# design.net
KiCad netlist of a schematic drawn in Altium Designer
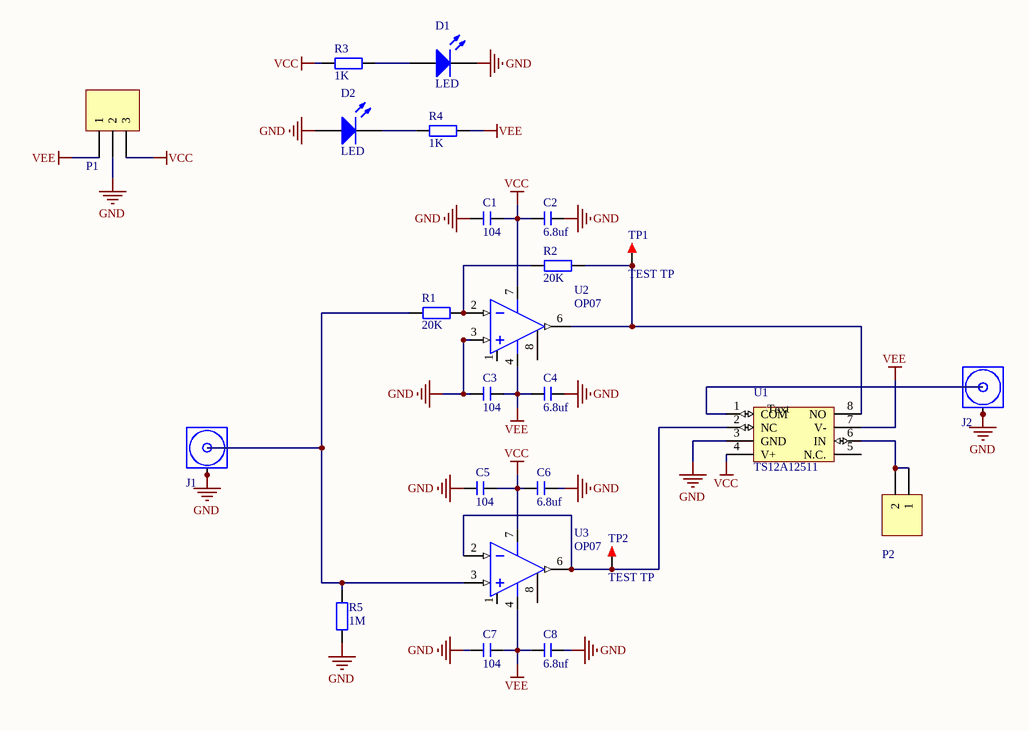
[diagram p0: 相敏检波器.SchDoc]

(export (version "E")
  (design (tool "Eeschema 10.0.6"))
  (components
    (comp (ref "C1")
      (value "104")
      (footprint "C 0805")
      (description "无极性贴片电容")
      (fields (field (name "版权归属") "源创客"))
      (libsource (lib "电阻-电容-电感") (part "C"))
    )
    (comp (ref "C2")
      (value "6.8uf")
      (footprint "C 0805")
      (description "无极性贴片电容")
      (fields (field (name "版权归属") "源创客"))
      (libsource (lib "电阻-电容-电感") (part "C"))
    )
    (comp (ref "C3")
      (value "104")
      (footprint "C 0805")
      (description "无极性贴片电容")
      (fields (field (name "版权归属") "源创客"))
      (libsource (lib "电阻-电容-电感") (part "C"))
    )
    (comp (ref "C4")
      (value "6.8uf")
      (footprint "C 0805")
      (description "无极性贴片电容")
      (fields (field (name "版权归属") "源创客"))
      (libsource (lib "电阻-电容-电感") (part "C"))
    )
    (comp (ref "C5")
      (value "104")
      (footprint "C 0805")
      (description "无极性贴片电容")
      (fields (field (name "版权归属") "源创客"))
      (libsource (lib "电阻-电容-电感") (part "C"))
    )
    (comp (ref "C6")
      (value "6.8uf")
      (footprint "C 0805")
      (description "无极性贴片电容")
      (fields (field (name "版权归属") "源创客"))
      (libsource (lib "电阻-电容-电感") (part "C"))
    )
    (comp (ref "C7")
      (value "104")
      (footprint "C 0805")
      (description "无极性贴片电容")
      (fields (field (name "版权归属") "源创客"))
      (libsource (lib "电阻-电容-电感") (part "C"))
    )
    (comp (ref "C8")
      (value "6.8uf")
      (footprint "C 0805")
      (description "无极性贴片电容")
      (fields (field (name "版权归属") "源创客"))
      (libsource (lib "电阻-电容-电感") (part "C"))
    )
    (comp (ref "D1")
      (value "LED")
      (footprint "LED_0805")
      (description "发光二极管")
      (fields (field (name "PUBLISHER") "Altium Limited"))
      (libsource (lib "LIB") (part "LED"))
    )
    (comp (ref "D2")
      (value "LED")
      (footprint "LED_0805")
      (description "发光二极管")
      (fields (field (name "PUBLISHER") "Altium Limited"))
      (libsource (lib "LIB") (part "LED"))
    )
    (comp (ref "J1") (value "COAX") (footprint "MCX5.08-5-H") (libsource (lib "LIB") (part "COAX")))
    (comp (ref "J2") (value "COAX") (footprint "MCX5.08-5-H") (libsource (lib "LIB") (part "COAX")))
    (comp (ref "P1")
      (value "Header 3")
      (footprint "HDR3X1_B2")
      (description "接插件")
      (fields (field (name "PUBLISHER") "Altium Limited"))
      (libsource (lib "LIB") (part "Header 3"))
    )
    (comp (ref "P2")
      (value "Header 2")
      (footprint "HDR2X1_B2")
      (description "接插件")
      (fields (field (name "PUBLISHER") "Altium Limited"))
      (libsource (lib "LIB") (part "Header 2"))
    )
    (comp (ref "R1")
      (value "20K")
      (footprint "R 0805")
      (description "贴片电阻")
      (fields (field (name "版权归属") "源创客"))
      (libsource (lib "电阻-电容-电感") (part "R"))
    )
    (comp (ref "R2")
      (value "20K")
      (footprint "R 0805")
      (description "贴片电阻")
      (fields (field (name "版权归属") "源创客"))
      (libsource (lib "电阻-电容-电感") (part "R"))
    )
    (comp (ref "R3")
      (value "1K")
      (footprint "R 0805")
      (description "贴片电阻")
      (fields (field (name "版权归属") "源创客"))
      (libsource (lib "电阻-电容-电感") (part "R"))
    )
    (comp (ref "R4")
      (value "1K")
      (footprint "R 0805")
      (description "贴片电阻")
      (fields (field (name "版权归属") "源创客"))
      (libsource (lib "电阻-电容-电感") (part "R"))
    )
    (comp (ref "R5")
      (value "1M")
      (footprint "R 0805")
      (description "贴片电阻")
      (fields (field (name "版权归属") "源创客"))
      (libsource (lib "电阻-电容-电感") (part "R"))
    )
    (comp (ref "TP1")
      (value "TEST TP")
      (footprint "TEST TP1.4_B")
      (description "测试环")
      (fields (field (name "版权归属") "源创客"))
      (libsource (lib "未分类器件") (part "TEST TP"))
    )
    (comp (ref "TP2")
      (value "TEST TP")
      (footprint "TEST TP1.4_B")
      (description "测试环")
      (fields (field (name "版权归属") "源创客"))
      (libsource (lib "未分类器件") (part "TEST TP"))
    )
    (comp (ref "U1")
      (value "TS12A12511")
      (footprint "SOT23-8N")
      (description "具有负信号功能的 5Ω 单通道 SPDT 开关")
      (libsource (lib "LIB") (part "TS12A12511"))
    )
    (comp (ref "U2")
      (value "OP07")
      (footprint "SO8_L")
      (description "Precision Operational Amplifiers")
      (libsource (lib "LIB") (part "OP07"))
    )
    (comp (ref "U3")
      (value "OP07")
      (footprint "SO8_L")
      (description "Precision Operational Amplifiers")
      (libsource (lib "LIB") (part "OP07"))
    )
  )
  (nets
    (net (code "1") (name "GND") (class "Default")
      (node (ref "C1") (pin "1") (pinfunction "1_1") (pintype "passive"))
      (node (ref "C2") (pin "2") (pinfunction "2_2") (pintype "passive"))
      (node (ref "C3") (pin "1") (pinfunction "1_1") (pintype "passive"))
      (node (ref "C4") (pin "2") (pinfunction "2_2") (pintype "passive"))
      (node (ref "C5") (pin "1") (pinfunction "1_1") (pintype "passive"))
      (node (ref "C6") (pin "2") (pinfunction "2_2") (pintype "passive"))
      (node (ref "C7") (pin "1") (pinfunction "1_1") (pintype "passive"))
      (node (ref "C8") (pin "2") (pinfunction "2_2") (pintype "passive"))
      (node (ref "D1") (pin "2") (pinfunction "K_2") (pintype "passive"))
      (node (ref "D2") (pin "1") (pinfunction "A_1") (pintype "passive"))
      (node (ref "J1") (pin "2") (pinfunction "GND_2") (pintype "passive"))
      (node (ref "J1") (pin "3") (pinfunction "GND_3") (pintype "passive"))
      (node (ref "J1") (pin "4") (pinfunction "GND_4") (pintype "passive"))
      (node (ref "J1") (pin "5") (pinfunction "GND_5") (pintype "passive"))
      (node (ref "J2") (pin "2") (pinfunction "GND_2") (pintype "passive"))
      (node (ref "J2") (pin "3") (pinfunction "GND_3") (pintype "passive"))
      (node (ref "J2") (pin "4") (pinfunction "GND_4") (pintype "passive"))
      (node (ref "J2") (pin "5") (pinfunction "GND_5") (pintype "passive"))
      (node (ref "P1") (pin "2") (pinfunction "2_2") (pintype "passive"))
      (node (ref "R5") (pin "1") (pinfunction "1_1") (pintype "passive"))
      (node (ref "U1") (pin "3") (pinfunction "GND_3") (pintype "power_in"))
      (node (ref "U2") (pin "3") (pinfunction "IN+_3") (pintype "input"))
    )
    (net (code "2") (name "Net-(D1-A)") (class "Default")
      (node (ref "D1") (pin "1") (pinfunction "A_1") (pintype "passive"))
      (node (ref "R3") (pin "2") (pinfunction "2_2") (pintype "passive"))
    )
    (net (code "3") (name "Net-(D2-K)") (class "Default")
      (node (ref "D2") (pin "2") (pinfunction "K_2") (pintype "passive"))
      (node (ref "R4") (pin "1") (pinfunction "1_1") (pintype "passive"))
    )
    (net (code "4") (name "Net-(J1-Signal)") (class "Default")
      (node (ref "J1") (pin "1") (pinfunction "Signal_1") (pintype "passive"))
      (node (ref "R1") (pin "1") (pinfunction "1_1") (pintype "passive"))
      (node (ref "R5") (pin "2") (pinfunction "2_2") (pintype "passive"))
      (node (ref "U3") (pin "3") (pinfunction "IN+_3") (pintype "input"))
    )
    (net (code "5") (name "Net-(J2-Signal)") (class "Default")
      (node (ref "J2") (pin "1") (pinfunction "Signal_1") (pintype "passive"))
      (node (ref "U1") (pin "1") (pinfunction "COM_1") (pintype "bidirectional"))
    )
    (net (code "6") (name "Net-(U1-IN)") (class "Default")
      (node (ref "P2") (pin "1") (pinfunction "1_1") (pintype "passive"))
      (node (ref "P2") (pin "2") (pinfunction "2_2") (pintype "passive"))
      (node (ref "U1") (pin "6") (pinfunction "IN_6") (pintype "bidirectional"))
    )
    (net (code "7") (name "Net-(U1-NC)") (class "Default")
      (node (ref "TP2") (pin "1") (pinfunction "1_1") (pintype "passive"))
      (node (ref "U1") (pin "2") (pinfunction "NC_2") (pintype "bidirectional"))
      (node (ref "U3") (pin "2") (pinfunction "IN-_2") (pintype "input"))
      (node (ref "U3") (pin "6") (pinfunction "OUT_6") (pintype "output"))
    )
    (net (code "8") (name "Net-(U1-NO)") (class "Default")
      (node (ref "R2") (pin "2") (pinfunction "2_2") (pintype "passive"))
      (node (ref "TP1") (pin "1") (pinfunction "1_1") (pintype "passive"))
      (node (ref "U1") (pin "8") (pinfunction "NO_8") (pintype "passive"))
      (node (ref "U2") (pin "6") (pinfunction "OUT_6") (pintype "output"))
    )
    (net (code "9") (name "Net-(U2-IN-)") (class "Default")
      (node (ref "R1") (pin "2") (pinfunction "2_2") (pintype "passive"))
      (node (ref "R2") (pin "1") (pinfunction "1_1") (pintype "passive"))
      (node (ref "U2") (pin "2") (pinfunction "IN-_2") (pintype "input"))
    )
    (net (code "10") (name "VCC") (class "Default")
      (node (ref "C1") (pin "2") (pinfunction "2_2") (pintype "passive"))
      (node (ref "C2") (pin "1") (pinfunction "1_1") (pintype "passive"))
      (node (ref "C5") (pin "2") (pinfunction "2_2") (pintype "passive"))
      (node (ref "C6") (pin "1") (pinfunction "1_1") (pintype "passive"))
      (node (ref "P1") (pin "3") (pinfunction "3_3") (pintype "passive"))
      (node (ref "R3") (pin "1") (pinfunction "1_1") (pintype "passive"))
      (node (ref "U1") (pin "4") (pinfunction "V+_4") (pintype "power_in"))
      (node (ref "U2") (pin "7") (pinfunction "V+_7") (pintype "power_in"))
      (node (ref "U3") (pin "7") (pinfunction "V+_7") (pintype "power_in"))
    )
    (net (code "11") (name "VEE") (class "Default")
      (node (ref "C3") (pin "2") (pinfunction "2_2") (pintype "passive"))
      (node (ref "C4") (pin "1") (pinfunction "1_1") (pintype "passive"))
      (node (ref "C7") (pin "2") (pinfunction "2_2") (pintype "passive"))
      (node (ref "C8") (pin "1") (pinfunction "1_1") (pintype "passive"))
      (node (ref "P1") (pin "1") (pinfunction "1_1") (pintype "passive"))
      (node (ref "R4") (pin "2") (pinfunction "2_2") (pintype "passive"))
      (node (ref "U1") (pin "7") (pinfunction "V-_7") (pintype "power_in"))
      (node (ref "U2") (pin "4") (pinfunction "V-_4") (pintype "power_in"))
      (node (ref "U3") (pin "4") (pinfunction "V-_4") (pintype "power_in"))
    )
    (net (code "12") (name "unconnected-(U1-N.C.-Pad5)") (class "Default")
      (node (ref "U1") (pin "5") (pinfunction "N.C._5") (pintype "power_in"))
    )
    (net (code "13") (name "unconnected-(U2-OFFSET_N1-Pad1)") (class "Default")
      (node (ref "U2") (pin "1") (pinfunction "OFFSET_N1_1") (pintype "passive"))
    )
    (net (code "14") (name "unconnected-(U2-OFFSET_N2-Pad8)") (class "Default")
      (node (ref "U2") (pin "8") (pinfunction "OFFSET_N2_8") (pintype "passive"))
    )
    (net (code "15") (name "unconnected-(U3-OFFSET_N1-Pad1)") (class "Default")
      (node (ref "U3") (pin "1") (pinfunction "OFFSET_N1_1") (pintype "passive"))
    )
    (net (code "16") (name "unconnected-(U3-OFFSET_N2-Pad8)") (class "Default")
      (node (ref "U3") (pin "8") (pinfunction "OFFSET_N2_8") (pintype "passive"))
    )
  )
)
